# RpiWeatherStationBoard.net
KiCad netlist of a schematic drawn in EAGLE
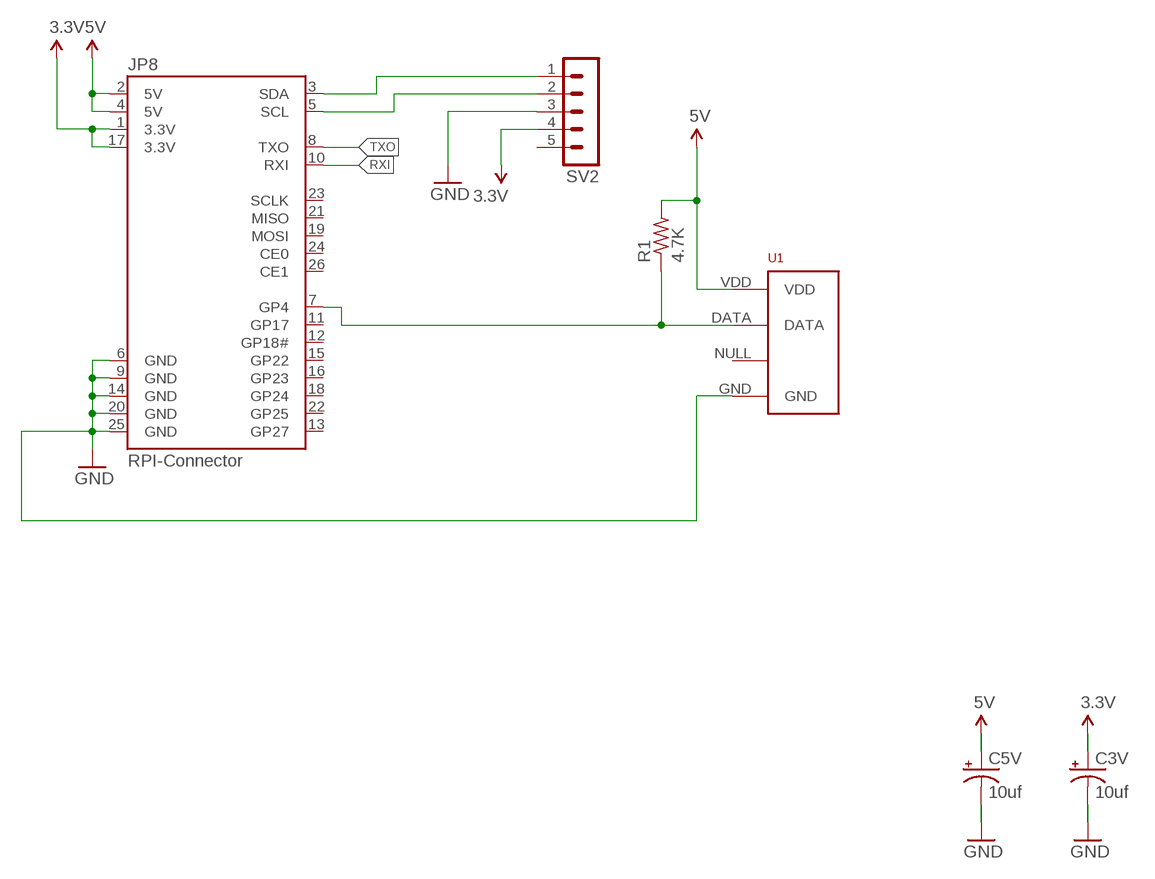
[diagram p0: schematic, sheet 1]

(export (version "E")
  (design (tool "Eeschema 10.0.6"))
  (components
    (comp (ref "C3V")
      (value "10uf")
      (footprint "eagle-import:CPOL-RADIAL-10UF-25V-KIT")
      (libsource (lib "eagle-import") (part "10UF-25V-20%(PTH)KIT"))
    )
    (comp (ref "C5V")
      (value "10uf")
      (footprint "eagle-import:CPOL-RADIAL-10UF-25V-KIT")
      (libsource (lib "eagle-import") (part "10UF-25V-20%(PTH)KIT"))
    )
    (comp (ref "JP8")
      (value "RPI-Connector")
      (footprint "eagle-import:2X13-SHROUDED")
      (libsource (lib "eagle-import") (part "RASPBERRYPI-GPIOPTH"))
    )
    (comp (ref "R1")
      (value "4.7K")
      (footprint "eagle-import:0207_10")
      (libsource (lib "eagle-import") (part "R-US_0207/10"))
    )
    (comp (ref "SV2")
      (value "MA05-1")
      (footprint "eagle-import:MA05-1")
      (libsource (lib "eagle-import") (part "MA05-1"))
    )
    (comp (ref "U1")
      (value "RHT03_DHT-22_AM2302WIRED")
      (footprint "eagle-import:AM2302")
      (libsource (lib "eagle-import") (part "RHT03_DHT-22_AM2302WIRED"))
    )
  )
  (nets
    (net (code "1") (name "3.3V") (class "Default")
      (node (ref "C3V") (pin "1") (pinfunction "+_1") (pintype "passive"))
      (node (ref "JP8") (pin "1") (pinfunction "3.3V_1") (pintype "power_in"))
      (node (ref "JP8") (pin "17") (pinfunction "3.3V_17") (pintype "power_in"))
      (node (ref "SV2") (pin "4") (pinfunction "4_4") (pintype "passive"))
    )
    (net (code "2") (name "5V") (class "Default")
      (node (ref "C5V") (pin "1") (pinfunction "+_1") (pintype "passive"))
      (node (ref "JP8") (pin "2") (pinfunction "5V_2") (pintype "power_in"))
      (node (ref "JP8") (pin "4") (pinfunction "5V_4") (pintype "power_in"))
      (node (ref "R1") (pin "2") (pinfunction "2_2") (pintype "passive"))
      (node (ref "U1") (pin "VDD") (pinfunction "VDD_VDD") (pintype "power_in"))
    )
    (net (code "3") (name "GND") (class "Default")
      (node (ref "C3V") (pin "2") (pinfunction "-_2") (pintype "passive"))
      (node (ref "C5V") (pin "2") (pinfunction "-_2") (pintype "passive"))
      (node (ref "JP8") (pin "14") (pinfunction "GND_14") (pintype "power_in"))
      (node (ref "JP8") (pin "20") (pinfunction "GND_20") (pintype "power_in"))
      (node (ref "JP8") (pin "25") (pinfunction "GND_25") (pintype "power_in"))
      (node (ref "JP8") (pin "6") (pinfunction "GND_6") (pintype "power_in"))
      (node (ref "JP8") (pin "9") (pinfunction "GND_9") (pintype "power_in"))
      (node (ref "SV2") (pin "3") (pinfunction "3_3") (pintype "passive"))
      (node (ref "U1") (pin "GND") (pinfunction "GND_GND") (pintype "power_in"))
    )
    (net (code "4") (name "Net-(JP8-GP4)") (class "Default")
      (node (ref "JP8") (pin "7") (pinfunction "GP4_7") (pintype "bidirectional"))
      (node (ref "R1") (pin "1") (pinfunction "1_1") (pintype "passive"))
      (node (ref "U1") (pin "DATA") (pinfunction "DATA_DATA") (pintype "bidirectional"))
    )
    (net (code "5") (name "Net-(JP8-SCL)") (class "Default")
      (node (ref "JP8") (pin "5") (pinfunction "SCL_5") (pintype "bidirectional"))
      (node (ref "SV2") (pin "2") (pinfunction "2_2") (pintype "passive"))
    )
    (net (code "6") (name "Net-(JP8-SDA)") (class "Default")
      (node (ref "JP8") (pin "3") (pinfunction "SDA_3") (pintype "bidirectional"))
      (node (ref "SV2") (pin "1") (pinfunction "1_1") (pintype "passive"))
    )
    (net (code "7") (name "RXI") (class "Default")
      (node (ref "JP8") (pin "10") (pinfunction "RXI_10") (pintype "input"))
    )
    (net (code "8") (name "TXO") (class "Default")
      (node (ref "JP8") (pin "8") (pinfunction "TXO_8") (pintype "output"))
    )
    (net (code "9") (name "unconnected-(JP8-CE0-Pad24)") (class "Default")
      (node (ref "JP8") (pin "24") (pinfunction "CE0_24") (pintype "output"))
    )
    (net (code "10") (name "unconnected-(JP8-CE1-Pad26)") (class "Default")
      (node (ref "JP8") (pin "26") (pinfunction "CE1_26") (pintype "output"))
    )
    (net (code "11") (name "unconnected-(JP8-GP17-Pad11)") (class "Default")
      (node (ref "JP8") (pin "11") (pinfunction "GP17_11") (pintype "bidirectional"))
    )
    (net (code "12") (name "unconnected-(JP8-GP18#-Pad12)") (class "Default")
      (node (ref "JP8") (pin "12") (pinfunction "GP18#_12") (pintype "bidirectional"))
    )
    (net (code "13") (name "unconnected-(JP8-GP22-Pad15)") (class "Default")
      (node (ref "JP8") (pin "15") (pinfunction "GP22_15") (pintype "bidirectional"))
    )
    (net (code "14") (name "unconnected-(JP8-GP23-Pad16)") (class "Default")
      (node (ref "JP8") (pin "16") (pinfunction "GP23_16") (pintype "bidirectional"))
    )
    (net (code "15") (name "unconnected-(JP8-GP24-Pad18)") (class "Default")
      (node (ref "JP8") (pin "18") (pinfunction "GP24_18") (pintype "bidirectional"))
    )
    (net (code "16") (name "unconnected-(JP8-GP25-Pad22)") (class "Default")
      (node (ref "JP8") (pin "22") (pinfunction "GP25_22") (pintype "bidirectional"))
    )
    (net (code "17") (name "unconnected-(JP8-GP27-Pad13)") (class "Default")
      (node (ref "JP8") (pin "13") (pinfunction "GP27_13") (pintype "bidirectional"))
    )
    (net (code "18") (name "unconnected-(JP8-MISO-Pad21)") (class "Default")
      (node (ref "JP8") (pin "21") (pinfunction "MISO_21") (pintype "input"))
    )
    (net (code "19") (name "unconnected-(JP8-MOSI-Pad19)") (class "Default")
      (node (ref "JP8") (pin "19") (pinfunction "MOSI_19") (pintype "output"))
    )
    (net (code "20") (name "unconnected-(JP8-SCLK-Pad23)") (class "Default")
      (node (ref "JP8") (pin "23") (pinfunction "SCLK_23") (pintype "output"))
    )
    (net (code "21") (name "unconnected-(SV2-Pad5)") (class "Default")
      (node (ref "SV2") (pin "5") (pinfunction "5_5") (pintype "passive"))
    )
    (net (code "22") (name "unconnected-(U1-PadNULL)") (class "Default")
      (node (ref "U1") (pin "NULL") (pinfunction "NULL_NULL") (pintype "no_connect"))
    )
  )
)
